# star.net
KiCad netlist of a schematic drawn in EAGLE
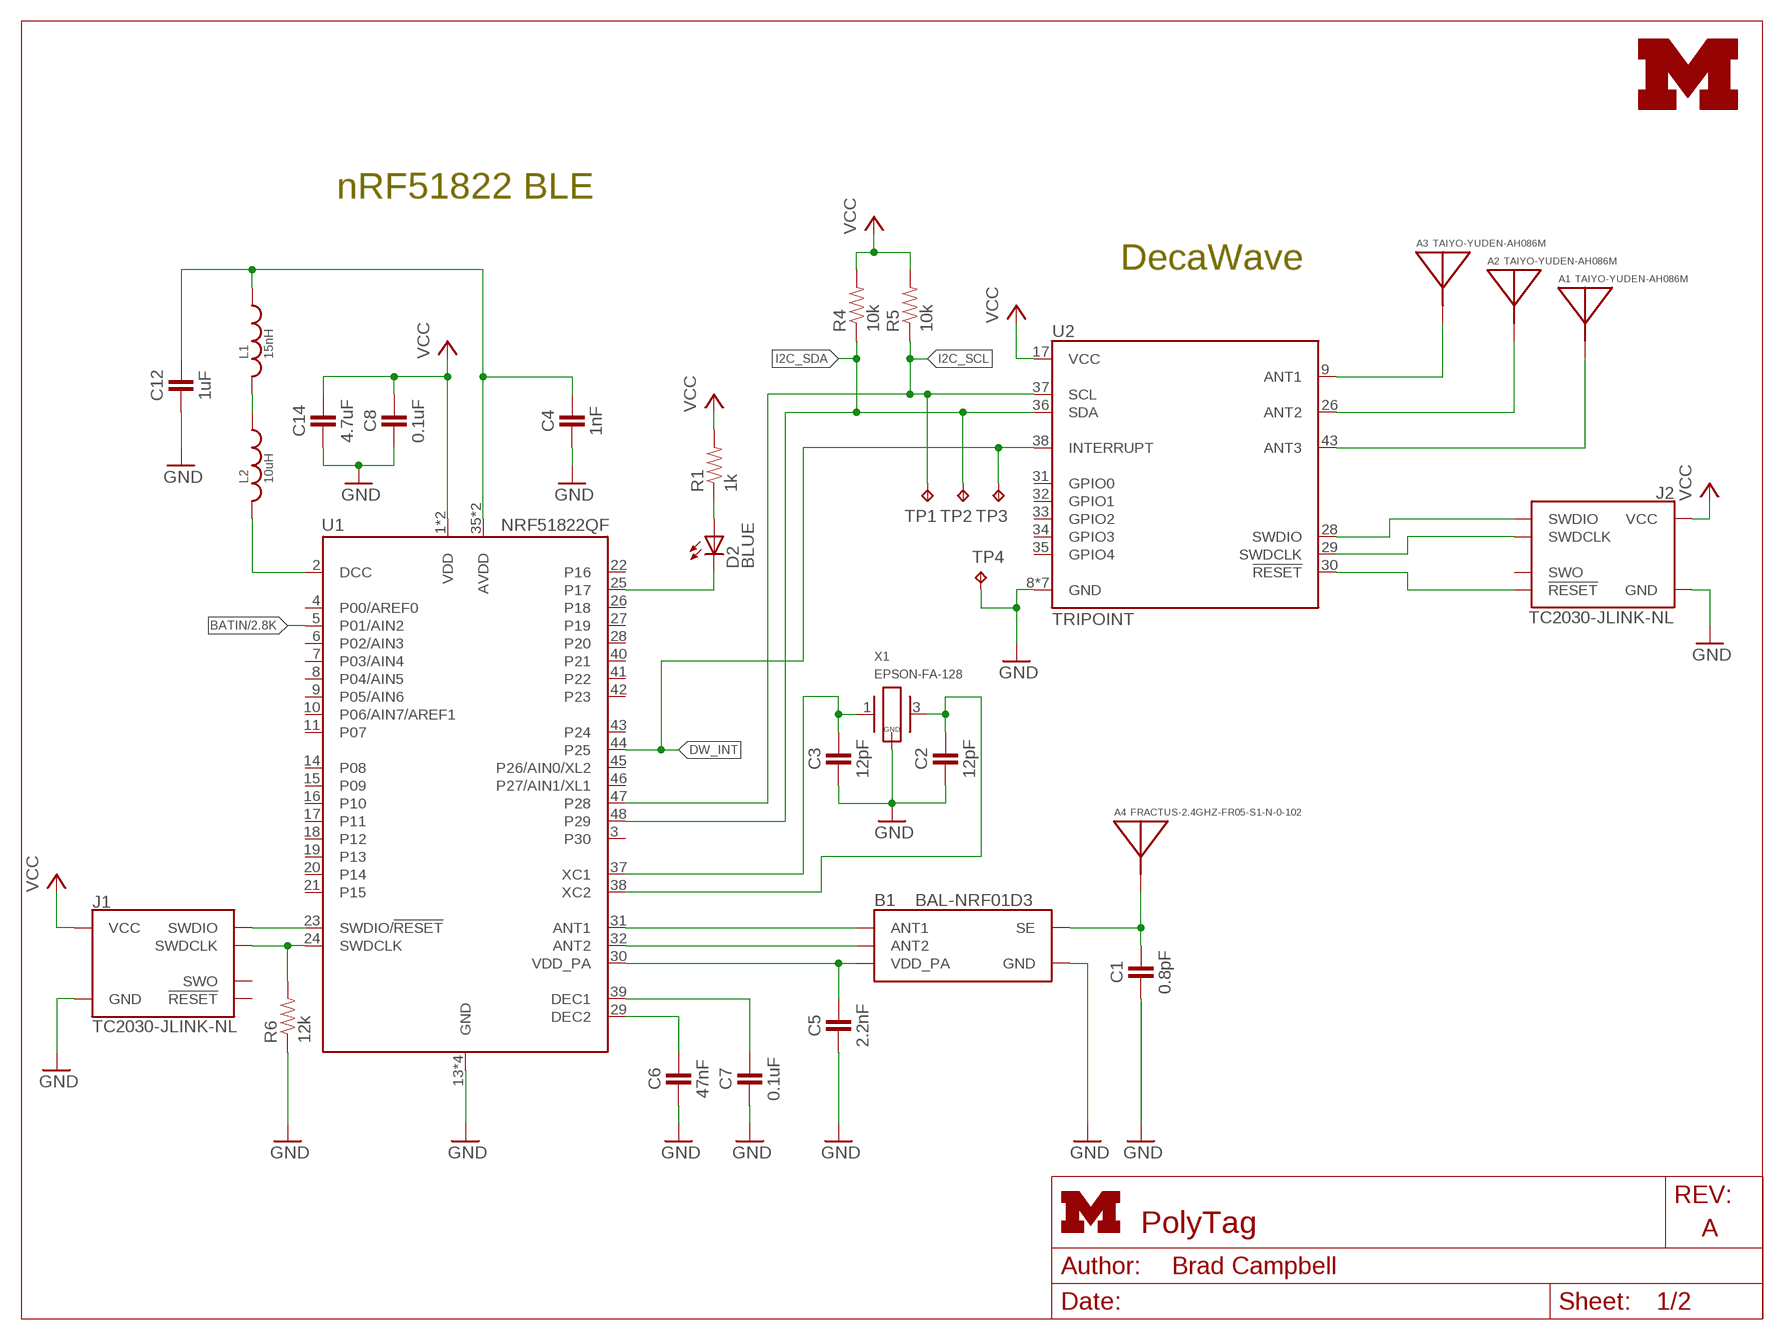
[diagram p0: schematic, sheet 1]
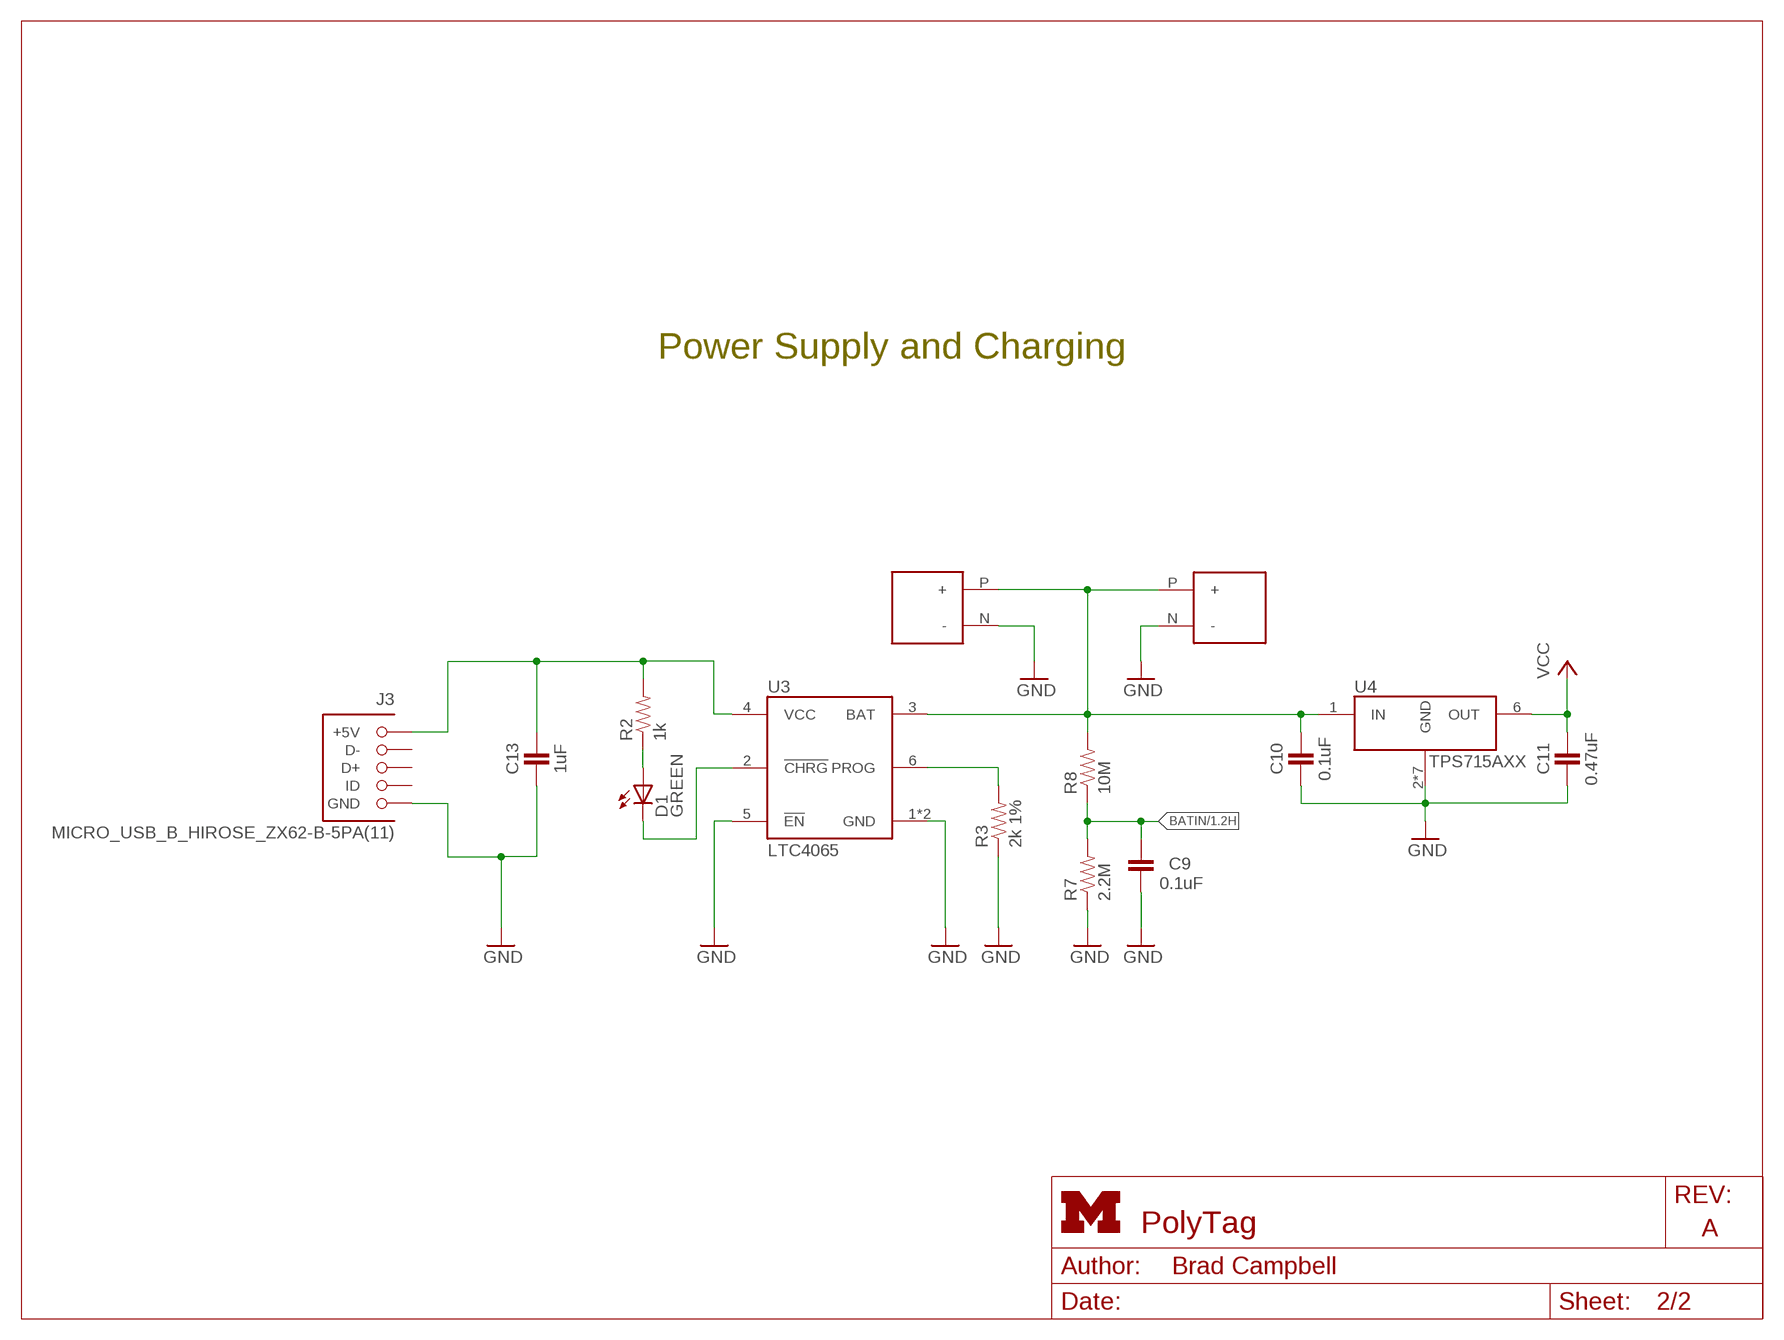
[diagram p1: schematic, sheet 2]

(export (version "E")
  (design (tool "Eeschema 10.0.6"))
  (components
    (comp (ref "A1")
      (value "TAIYO-YUDEN-AH086M")
      (footprint "eagle-import:TAIYO-YUDEN-AH086M")
      (libsource (lib "eagle-import") (part "TAIYO-YUDEN-AH086M"))
    )
    (comp (ref "A2")
      (value "TAIYO-YUDEN-AH086M")
      (footprint "eagle-import:TAIYO-YUDEN-AH086M")
      (libsource (lib "eagle-import") (part "TAIYO-YUDEN-AH086M"))
    )
    (comp (ref "A3")
      (value "TAIYO-YUDEN-AH086M")
      (footprint "eagle-import:TAIYO-YUDEN-AH086M")
      (libsource (lib "eagle-import") (part "TAIYO-YUDEN-AH086M"))
    )
    (comp (ref "A4")
      (value "FRACTUS-2.4GHZ-FR05-S1-N-0-102")
      (footprint "eagle-import:FRACTUS-ANTENNA-FR05-S1-N-0-102")
      (libsource (lib "eagle-import") (part "FRACTUS-2.4GHZ-FR05-S1-N-0-102"))
    )
    (comp (ref "B1")
      (value "BAL-NRF01D3")
      (footprint "eagle-import:BAL-NRF01D3")
      (libsource (lib "eagle-import") (part "BAL-NRF01D3"))
    )
    (comp (ref "C1")
      (value "0.8pF")
      (footprint "eagle-import:0402_CAP")
      (libsource (lib "eagle-import") (part "CAPACITOR"))
    )
    (comp (ref "C2")
      (value "12pF")
      (footprint "eagle-import:0402_CAP")
      (libsource (lib "eagle-import") (part "CAPACITOR"))
    )
    (comp (ref "C3")
      (value "12pF")
      (footprint "eagle-import:0402_CAP")
      (libsource (lib "eagle-import") (part "CAPACITOR"))
    )
    (comp (ref "C4")
      (value "1nF")
      (footprint "eagle-import:0402_CAP")
      (libsource (lib "eagle-import") (part "CAPACITOR"))
    )
    (comp (ref "C5")
      (value "2.2nF")
      (footprint "eagle-import:0402_CAP")
      (libsource (lib "eagle-import") (part "CAPACITOR"))
    )
    (comp (ref "C6")
      (value "47nF")
      (footprint "eagle-import:0402_CAP")
      (libsource (lib "eagle-import") (part "CAPACITOR"))
    )
    (comp (ref "C7")
      (value "0.1uF")
      (footprint "eagle-import:0402_CAP")
      (libsource (lib "eagle-import") (part "CAPACITOR"))
    )
    (comp (ref "C8")
      (value "0.1uF")
      (footprint "eagle-import:0402_CAP")
      (libsource (lib "eagle-import") (part "CAPACITOR"))
    )
    (comp (ref "C12")
      (value "1uF")
      (footprint "eagle-import:0402_CAP")
      (libsource (lib "eagle-import") (part "CAPACITOR"))
    )
    (comp (ref "C14")
      (value "4.7uF")
      (footprint "eagle-import:0402_CAP")
      (libsource (lib "eagle-import") (part "CAPACITOR"))
    )
    (comp (ref "D2")
      (value "BLUE")
      (footprint "eagle-import:LED-0603")
      (libsource (lib "eagle-import") (part "LED0603"))
    )
    (comp (ref "J1")
      (value "TC2030-JLINK-NL")
      (footprint "eagle-import:TC2030-IDC-NL")
      (libsource (lib "eagle-import") (part "TC2030-JLINK-NL"))
    )
    (comp (ref "J2")
      (value "TC2030-JLINK-NL")
      (footprint "eagle-import:TC2030-IDC-NL")
      (libsource (lib "eagle-import") (part "TC2030-JLINK-NL"))
    )
    (comp (ref "L1")
      (value "15nH")
      (footprint "eagle-import:0402_CAP")
      (libsource (lib "eagle-import") (part "INDUCTOR0402"))
    )
    (comp (ref "L2")
      (value "10uH")
      (footprint "eagle-import:0603_CAP")
      (libsource (lib "eagle-import") (part "INDUCTOR0603"))
    )
    (comp (ref "LOGO1")
      (value "UMICH_SOLID_SMALL")
      (footprint "eagle-import:UMICH_SOLID_75MIL")
      (libsource (lib "eagle-import") (part "UMICH_SOLID_SMALL"))
    )
    (comp (ref "R1")
      (value "1k")
      (footprint "eagle-import:0402_RES")
      (libsource (lib "eagle-import") (part "RESISTOR0402_RES"))
    )
    (comp (ref "R4")
      (value "10k")
      (footprint "eagle-import:0402_RES")
      (libsource (lib "eagle-import") (part "RESISTOR0402_RES"))
    )
    (comp (ref "R5")
      (value "10k")
      (footprint "eagle-import:0402_RES")
      (libsource (lib "eagle-import") (part "RESISTOR0402_RES"))
    )
    (comp (ref "R6")
      (value "12k")
      (footprint "eagle-import:0402_RES")
      (libsource (lib "eagle-import") (part "RESISTOR0402_RES"))
    )
    (comp (ref "TP1")
      (value "TPTP06SQ")
      (footprint "eagle-import:TP06SQ")
      (libsource (lib "eagle-import") (part "TPTP06SQ"))
    )
    (comp (ref "TP2")
      (value "TPTP06SQ")
      (footprint "eagle-import:TP06SQ")
      (libsource (lib "eagle-import") (part "TPTP06SQ"))
    )
    (comp (ref "TP3")
      (value "TPTP06SQ")
      (footprint "eagle-import:TP06SQ")
      (libsource (lib "eagle-import") (part "TPTP06SQ"))
    )
    (comp (ref "TP4")
      (value "TPTP06SQ")
      (footprint "eagle-import:TP06SQ")
      (libsource (lib "eagle-import") (part "TPTP06SQ"))
    )
    (comp (ref "U1")
      (value "NRF51822QF")
      (footprint "eagle-import:QFN-48-6MM")
      (libsource (lib "eagle-import") (part "NRF51822QF"))
    )
    (comp (ref "U2")
      (value "TRIPOINT")
      (footprint "eagle-import:TRIPOINT")
      (libsource (lib "eagle-import") (part "TRIPOINT"))
    )
    (comp (ref "X1")
      (value "EPSON-FA-128")
      (footprint "eagle-import:FA-128")
      (libsource (lib "eagle-import") (part "EPSON-FA-128"))
    )
    (comp (ref "C9")
      (value "0.1uF")
      (footprint "eagle-import:0402_CAP")
      (libsource (lib "eagle-import") (part "CAPACITOR"))
    )
    (comp (ref "C10")
      (value "0.1uF")
      (footprint "eagle-import:0402_CAP")
      (libsource (lib "eagle-import") (part "CAPACITOR"))
    )
    (comp (ref "C11")
      (value "0.47uF")
      (footprint "eagle-import:0402_CAP")
      (libsource (lib "eagle-import") (part "CAPACITOR"))
    )
    (comp (ref "C13")
      (value "1uF")
      (footprint "eagle-import:0402_CAP")
      (libsource (lib "eagle-import") (part "CAPACITOR"))
    )
    (comp (ref "D1")
      (value "GREEN")
      (footprint "eagle-import:LED-0603")
      (libsource (lib "eagle-import") (part "LED0603"))
    )
    (comp (ref "J3")
      (value "MICRO_USB_B_HIROSE_ZX62-B-5PA(11)")
      (footprint "eagle-import:USB_MICRO_B-HIROSE-ZX62-B-5PA(11)")
      (libsource (lib "eagle-import") (part "MICRO_USB_B_HIROSE_ZX62-B-5PA(11)"))
    )
    (comp (ref "J4")
      (value "BAT_HOLE")
      (footprint "eagle-import:BATTERY_HOLE")
      (libsource (lib "eagle-import") (part "BAT_HOLE"))
    )
    (comp (ref "J5")
      (value "BAT_HOLE")
      (footprint "eagle-import:BATTERY_HOLE")
      (libsource (lib "eagle-import") (part "BAT_HOLE"))
    )
    (comp (ref "R2")
      (value "1k")
      (footprint "eagle-import:0402_RES")
      (libsource (lib "eagle-import") (part "RESISTOR0402_RES"))
    )
    (comp (ref "R3")
      (value "2k 1%")
      (footprint "eagle-import:0402_RES")
      (libsource (lib "eagle-import") (part "RESISTOR0402_RES"))
    )
    (comp (ref "R7")
      (value "2.2M")
      (footprint "eagle-import:0402_RES")
      (libsource (lib "eagle-import") (part "RESISTOR0402_RES"))
    )
    (comp (ref "R8")
      (value "10M")
      (footprint "eagle-import:0402_RES")
      (libsource (lib "eagle-import") (part "RESISTOR0402_RES"))
    )
    (comp (ref "U3")
      (value "LTC4065")
      (footprint "eagle-import:DFN-6_2MM")
      (libsource (lib "eagle-import") (part "LTC4065"))
    )
    (comp (ref "U4")
      (value "TPS715AXX")
      (footprint "eagle-import:WDFN-6")
      (libsource (lib "eagle-import") (part "TPS715AXX"))
    )
  )
  (nets
    (net (code "1") (name "BATIN") (class "Default")
      (node (ref "C9") (pin "2") (pinfunction "2_2") (pintype "bidirectional"))
      (node (ref "R7") (pin "2") (pinfunction "2_2") (pintype "passive"))
      (node (ref "R8") (pin "1") (pinfunction "1_1") (pintype "passive"))
      (node (ref "U1") (pin "5") (pinfunction "P01/AIN2_5") (pintype "bidirectional"))
    )
    (net (code "2") (name "DW_INT") (class "Default")
      (node (ref "TP3") (pin "TP") (pinfunction "TP_TP") (pintype "input"))
      (node (ref "U1") (pin "44") (pinfunction "P25_44") (pintype "bidirectional"))
      (node (ref "U2") (pin "38") (pinfunction "INTERRUPT_38") (pintype "bidirectional"))
    )
    (net (code "3") (name "GND") (class "Default")
      (node (ref "B1") (pin "GND") (pinfunction "GND_GND") (pintype "bidirectional"))
      (node (ref "C1") (pin "2") (pinfunction "2_2") (pintype "bidirectional"))
      (node (ref "C10") (pin "2") (pinfunction "2_2") (pintype "bidirectional"))
      (node (ref "C11") (pin "2") (pinfunction "2_2") (pintype "bidirectional"))
      (node (ref "C12") (pin "2") (pinfunction "2_2") (pintype "bidirectional"))
      (node (ref "C13") (pin "2") (pinfunction "2_2") (pintype "bidirectional"))
      (node (ref "C14") (pin "2") (pinfunction "2_2") (pintype "bidirectional"))
      (node (ref "C2") (pin "2") (pinfunction "2_2") (pintype "bidirectional"))
      (node (ref "C3") (pin "2") (pinfunction "2_2") (pintype "bidirectional"))
      (node (ref "C4") (pin "2") (pinfunction "2_2") (pintype "bidirectional"))
      (node (ref "C5") (pin "2") (pinfunction "2_2") (pintype "bidirectional"))
      (node (ref "C6") (pin "2") (pinfunction "2_2") (pintype "bidirectional"))
      (node (ref "C7") (pin "2") (pinfunction "2_2") (pintype "bidirectional"))
      (node (ref "C8") (pin "2") (pinfunction "2_2") (pintype "bidirectional"))
      (node (ref "C9") (pin "1") (pinfunction "1_1") (pintype "bidirectional"))
      (node (ref "J1") (pin "5") (pinfunction "GND_5") (pintype "bidirectional"))
      (node (ref "J2") (pin "5") (pinfunction "GND_5") (pintype "bidirectional"))
      (node (ref "J3") (pin "5") (pinfunction "GND_5") (pintype "bidirectional"))
      (node (ref "J4") (pin "N") (pinfunction "-_N") (pintype "bidirectional"))
      (node (ref "J5") (pin "N") (pinfunction "-_N") (pintype "bidirectional"))
      (node (ref "R3") (pin "1") (pinfunction "1_1") (pintype "passive"))
      (node (ref "R6") (pin "1") (pinfunction "1_1") (pintype "passive"))
      (node (ref "R7") (pin "1") (pinfunction "1_1") (pintype "passive"))
      (node (ref "TP4") (pin "TP") (pinfunction "TP_TP") (pintype "input"))
      (node (ref "U1") (pin "13") (pinfunction "GND_13") (pintype "bidirectional"))
      (node (ref "U1") (pin "33") (pinfunction "GND_33") (pintype "bidirectional"))
      (node (ref "U1") (pin "34") (pinfunction "GND_34") (pintype "bidirectional"))
      (node (ref "U1") (pin "GND") (pinfunction "GND_GND") (pintype "bidirectional"))
      (node (ref "U2") (pin "10") (pinfunction "GND_10") (pintype "bidirectional"))
      (node (ref "U2") (pin "18") (pinfunction "GND_18") (pintype "bidirectional"))
      (node (ref "U2") (pin "25") (pinfunction "GND_25") (pintype "bidirectional"))
      (node (ref "U2") (pin "27") (pinfunction "GND_27") (pintype "bidirectional"))
      (node (ref "U2") (pin "42") (pinfunction "GND_42") (pintype "bidirectional"))
      (node (ref "U2") (pin "44") (pinfunction "GND_44") (pintype "bidirectional"))
      (node (ref "U2") (pin "8") (pinfunction "GND_8") (pintype "bidirectional"))
      (node (ref "U3") (pin "1") (pinfunction "GND_1") (pintype "bidirectional"))
      (node (ref "U3") (pin "5") (pinfunction "~{EN}_5") (pintype "bidirectional"))
      (node (ref "U3") (pin "7") (pinfunction "GND_7") (pintype "bidirectional"))
      (node (ref "U4") (pin "2") (pinfunction "GND_2") (pintype "bidirectional"))
      (node (ref "U4") (pin "3") (pinfunction "GND_3") (pintype "bidirectional"))
      (node (ref "U4") (pin "4") (pinfunction "GND_4") (pintype "bidirectional"))
      (node (ref "U4") (pin "5") (pinfunction "GND_5") (pintype "bidirectional"))
      (node (ref "U4") (pin "TP") (pinfunction "GND_TP") (pintype "bidirectional"))
      (node (ref "U4") (pin "TP2") (pinfunction "GND_TP2") (pintype "bidirectional"))
      (node (ref "U4") (pin "TP3") (pinfunction "GND_TP3") (pintype "bidirectional"))
      (node (ref "X1") (pin "2") (pinfunction "GND_2") (pintype "bidirectional"))
      (node (ref "X1") (pin "4") (pinfunction "GND_4") (pintype "bidirectional"))
    )
    (net (code "4") (name "I2C_SCL") (class "Default")
      (node (ref "R5") (pin "1") (pinfunction "1_1") (pintype "passive"))
      (node (ref "TP1") (pin "TP") (pinfunction "TP_TP") (pintype "input"))
      (node (ref "U1") (pin "47") (pinfunction "P28_47") (pintype "bidirectional"))
      (node (ref "U2") (pin "37") (pinfunction "SCL_37") (pintype "bidirectional"))
    )
    (net (code "5") (name "I2C_SDA") (class "Default")
      (node (ref "R4") (pin "1") (pinfunction "1_1") (pintype "passive"))
      (node (ref "TP2") (pin "TP") (pinfunction "TP_TP") (pintype "input"))
      (node (ref "U1") (pin "48") (pinfunction "P29_48") (pintype "bidirectional"))
      (node (ref "U2") (pin "36") (pinfunction "SDA_36") (pintype "bidirectional"))
    )
    (net (code "6") (name "Net-(A1-ANTENNA)") (class "Default")
      (node (ref "A1") (pin "A") (pinfunction "ANTENNA_A") (pintype "bidirectional"))
      (node (ref "U2") (pin "43") (pinfunction "ANT3_43") (pintype "bidirectional"))
    )
    (net (code "7") (name "Net-(A2-ANTENNA)") (class "Default")
      (node (ref "A2") (pin "A") (pinfunction "ANTENNA_A") (pintype "bidirectional"))
      (node (ref "U2") (pin "26") (pinfunction "ANT2_26") (pintype "bidirectional"))
    )
    (net (code "8") (name "Net-(A3-ANTENNA)") (class "Default")
      (node (ref "A3") (pin "A") (pinfunction "ANTENNA_A") (pintype "bidirectional"))
      (node (ref "U2") (pin "9") (pinfunction "ANT1_9") (pintype "bidirectional"))
    )
    (net (code "9") (name "Net-(A4-ANTENNA)") (class "Default")
      (node (ref "A4") (pin "1") (pinfunction "ANTENNA_1") (pintype "bidirectional"))
      (node (ref "B1") (pin "SE") (pinfunction "SE_SE") (pintype "bidirectional"))
      (node (ref "C1") (pin "1") (pinfunction "1_1") (pintype "bidirectional"))
    )
    (net (code "10") (name "Net-(B1-VDD_PA)") (class "Default")
      (node (ref "B1") (pin "VCC") (pinfunction "VDD_PA_VCC") (pintype "bidirectional"))
      (node (ref "C5") (pin "1") (pinfunction "1_1") (pintype "bidirectional"))
      (node (ref "U1") (pin "30") (pinfunction "VDD_PA_30") (pintype "bidirectional"))
    )
    (net (code "11") (name "Net-(C12-Pad1)") (class "Default")
      (node (ref "C12") (pin "1") (pinfunction "1_1") (pintype "bidirectional"))
      (node (ref "C4") (pin "1") (pinfunction "1_1") (pintype "bidirectional"))
      (node (ref "L1") (pin "1") (pinfunction "1_1") (pintype "bidirectional"))
      (node (ref "U1") (pin "35") (pinfunction "AVDD_35") (pintype "bidirectional"))
      (node (ref "U1") (pin "36") (pinfunction "AVDD_36") (pintype "bidirectional"))
    )
    (net (code "12") (name "Net-(D1-PadA)") (class "Default")
      (node (ref "D1") (pin "A") (pinfunction "A_A") (pintype "passive"))
      (node (ref "R2") (pin "1") (pinfunction "1_1") (pintype "passive"))
    )
    (net (code "13") (name "Net-(D2-PadA)") (class "Default")
      (node (ref "D2") (pin "A") (pinfunction "A_A") (pintype "passive"))
      (node (ref "R1") (pin "1") (pinfunction "1_1") (pintype "passive"))
    )
    (net (code "14") (name "Net-(J1-SWDCLK)") (class "Default")
      (node (ref "J1") (pin "4") (pinfunction "SWDCLK_4") (pintype "bidirectional"))
      (node (ref "R6") (pin "2") (pinfunction "2_2") (pintype "passive"))
      (node (ref "U1") (pin "24") (pinfunction "SWDCLK_24") (pintype "bidirectional"))
    )
    (net (code "15") (name "Net-(J1-SWDIO)") (class "Default")
      (node (ref "J1") (pin "2") (pinfunction "SWDIO_2") (pintype "bidirectional"))
      (node (ref "U1") (pin "23") (pinfunction "SWDIO/~{RESET}_23") (pintype "bidirectional"))
    )
    (net (code "16") (name "Net-(J2-SWDCLK)") (class "Default")
      (node (ref "J2") (pin "4") (pinfunction "SWDCLK_4") (pintype "bidirectional"))
      (node (ref "U2") (pin "29") (pinfunction "SWDCLK_29") (pintype "bidirectional"))
    )
    (net (code "17") (name "Net-(J2-SWDIO)") (class "Default")
      (node (ref "J2") (pin "2") (pinfunction "SWDIO_2") (pintype "bidirectional"))
      (node (ref "U2") (pin "28") (pinfunction "SWDIO_28") (pintype "bidirectional"))
    )
    (net (code "18") (name "Net-(J2-~{RESET})") (class "Default")
      (node (ref "J2") (pin "3") (pinfunction "~{RESET}_3") (pintype "bidirectional"))
      (node (ref "U2") (pin "30") (pinfunction "~{RESET}_30") (pintype "bidirectional"))
    )
    (net (code "19") (name "Net-(J3-+5V)") (class "Default")
      (node (ref "C13") (pin "1") (pinfunction "1_1") (pintype "bidirectional"))
      (node (ref "J3") (pin "1") (pinfunction "+5V_1") (pintype "bidirectional"))
      (node (ref "R2") (pin "2") (pinfunction "2_2") (pintype "passive"))
      (node (ref "U3") (pin "4") (pinfunction "VCC_4") (pintype "bidirectional"))
    )
    (net (code "20") (name "Net-(J4-+)") (class "Default")
      (node (ref "C10") (pin "1") (pinfunction "1_1") (pintype "bidirectional"))
      (node (ref "J4") (pin "P") (pinfunction "+_P") (pintype "bidirectional"))
      (node (ref "J5") (pin "P") (pinfunction "+_P") (pintype "bidirectional"))
      (node (ref "R8") (pin "2") (pinfunction "2_2") (pintype "passive"))
      (node (ref "U3") (pin "3") (pinfunction "BAT_3") (pintype "bidirectional"))
      (node (ref "U4") (pin "1") (pinfunction "IN_1") (pintype "bidirectional"))
    )
    (net (code "21") (name "Net-(L1-Pad2)") (class "Default")
      (node (ref "L1") (pin "2") (pinfunction "2_2") (pintype "bidirectional"))
      (node (ref "L2") (pin "1") (pinfunction "1_1") (pintype "bidirectional"))
    )
    (net (code "22") (name "Net-(U1-ANT1)") (class "Default")
      (node (ref "B1") (pin "ANT1") (pinfunction "ANT1_ANT1") (pintype "bidirectional"))
      (node (ref "U1") (pin "31") (pinfunction "ANT1_31") (pintype "bidirectional"))
    )
    (net (code "23") (name "Net-(U1-ANT2)") (class "Default")
      (node (ref "B1") (pin "ANT2") (pinfunction "ANT2_ANT2") (pintype "bidirectional"))
      (node (ref "U1") (pin "32") (pinfunction "ANT2_32") (pintype "bidirectional"))
    )
    (net (code "24") (name "Net-(U1-DCC)") (class "Default")
      (node (ref "L2") (pin "2") (pinfunction "2_2") (pintype "bidirectional"))
      (node (ref "U1") (pin "2") (pinfunction "DCC_2") (pintype "bidirectional"))
    )
    (net (code "25") (name "Net-(U1-DEC1)") (class "Default")
      (node (ref "C7") (pin "1") (pinfunction "1_1") (pintype "bidirectional"))
      (node (ref "U1") (pin "39") (pinfunction "DEC1_39") (pintype "bidirectional"))
    )
    (net (code "26") (name "Net-(U1-DEC2)") (class "Default")
      (node (ref "C6") (pin "1") (pinfunction "1_1") (pintype "bidirectional"))
      (node (ref "U1") (pin "29") (pinfunction "DEC2_29") (pintype "bidirectional"))
    )
    (net (code "27") (name "Net-(U1-P17)") (class "Default")
      (node (ref "D2") (pin "C") (pinfunction "C_C") (pintype "passive"))
      (node (ref "U1") (pin "25") (pinfunction "P17_25") (pintype "bidirectional"))
    )
    (net (code "28") (name "Net-(U1-XC1)") (class "Default")
      (node (ref "C3") (pin "1") (pinfunction "1_1") (pintype "bidirectional"))
      (node (ref "U1") (pin "37") (pinfunction "XC1_37") (pintype "bidirectional"))
      (node (ref "X1") (pin "1") (pinfunction "1_1") (pintype "bidirectional"))
    )
    (net (code "29") (name "Net-(U1-XC2)") (class "Default")
      (node (ref "C2") (pin "1") (pinfunction "1_1") (pintype "bidirectional"))
      (node (ref "U1") (pin "38") (pinfunction "XC2_38") (pintype "bidirectional"))
      (node (ref "X1") (pin "3") (pinfunction "2_3") (pintype "bidirectional"))
    )
    (net (code "30") (name "Net-(U3-PROG)") (class "Default")
      (node (ref "R3") (pin "2") (pinfunction "2_2") (pintype "passive"))
      (node (ref "U3") (pin "6") (pinfunction "PROG_6") (pintype "bidirectional"))
    )
    (net (code "31") (name "Net-(U3-~{CHRG})") (class "Default")
      (node (ref "D1") (pin "C") (pinfunction "C_C") (pintype "passive"))
      (node (ref "U3") (pin "2") (pinfunction "~{CHRG}_2") (pintype "bidirectional"))
    )
    (net (code "32") (name "VCC") (class "Default")
      (node (ref "C11") (pin "1") (pinfunction "1_1") (pintype "bidirectional"))
      (node (ref "C14") (pin "1") (pinfunction "1_1") (pintype "bidirectional"))
      (node (ref "C8") (pin "1") (pinfunction "1_1") (pintype "bidirectional"))
      (node (ref "J1") (pin "1") (pinfunction "VCC_1") (pintype "bidirectional"))
      (node (ref "J2") (pin "1") (pinfunction "VCC_1") (pintype "bidirectional"))
      (node (ref "R1") (pin "2") (pinfunction "2_2") (pintype "passive"))
      (node (ref "R4") (pin "2") (pinfunction "2_2") (pintype "passive"))
      (node (ref "R5") (pin "2") (pinfunction "2_2") (pintype "passive"))
      (node (ref "U1") (pin "1") (pinfunction "VDD_1") (pintype "bidirectional"))
      (node (ref "U1") (pin "12") (pinfunction "VDD_12") (pintype "bidirectional"))
      (node (ref "U2") (pin "17") (pinfunction "VCC_17") (pintype "bidirectional"))
      (node (ref "U4") (pin "6") (pinfunction "OUT_6") (pintype "bidirectional"))
    )
    (net (code "33") (name "unconnected-(J1-SWO-Pad6)") (class "Default")
      (node (ref "J1") (pin "6") (pinfunction "SWO_6") (pintype "bidirectional"))
    )
    (net (code "34") (name "unconnected-(J1-~{RESET}-Pad3)") (class "Default")
      (node (ref "J1") (pin "3") (pinfunction "~{RESET}_3") (pintype "bidirectional"))
    )
    (net (code "35") (name "unconnected-(J2-SWO-Pad6)") (class "Default")
      (node (ref "J2") (pin "6") (pinfunction "SWO_6") (pintype "bidirectional"))
    )
    (net (code "36") (name "unconnected-(J3-D+-Pad3)") (class "Default")
      (node (ref "J3") (pin "3") (pinfunction "D+_3") (pintype "bidirectional"))
    )
    (net (code "37") (name "unconnected-(J3-D--Pad2)") (class "Default")
      (node (ref "J3") (pin "2") (pinfunction "D-_2") (pintype "bidirectional"))
    )
    (net (code "38") (name "unconnected-(J3-ID-Pad4)") (class "Default")
      (node (ref "J3") (pin "4") (pinfunction "ID_4") (pintype "bidirectional"))
    )
    (net (code "39") (name "unconnected-(U1-P00{slash}AREF0-Pad4)") (class "Default")
      (node (ref "U1") (pin "4") (pinfunction "P00/AREF0_4") (pintype "bidirectional"))
    )
    (net (code "40") (name "unconnected-(U1-P02{slash}AIN3-Pad6)") (class "Default")
      (node (ref "U1") (pin "6") (pinfunction "P02/AIN3_6") (pintype "bidirectional"))
    )
    (net (code "41") (name "unconnected-(U1-P03{slash}AIN4-Pad7)") (class "Default")
      (node (ref "U1") (pin "7") (pinfunction "P03/AIN4_7") (pintype "bidirectional"))
    )
    (net (code "42") (name "unconnected-(U1-P04{slash}AIN5-Pad8)") (class "Default")
      (node (ref "U1") (pin "8") (pinfunction "P04/AIN5_8") (pintype "bidirectional"))
    )
    (net (code "43") (name "unconnected-(U1-P05{slash}AIN6-Pad9)") (class "Default")
      (node (ref "U1") (pin "9") (pinfunction "P05/AIN6_9") (pintype "bidirectional"))
    )
    (net (code "44") (name "unconnected-(U1-P06{slash}AIN7{slash}AREF1-Pad10)") (class "Default")
      (node (ref "U1") (pin "10") (pinfunction "P06/AIN7/AREF1_10") (pintype "bidirectional"))
    )
    (net (code "45") (name "unconnected-(U1-P07-Pad11)") (class "Default")
      (node (ref "U1") (pin "11") (pinfunction "P07_11") (pintype "bidirectional"))
    )
    (net (code "46") (name "unconnected-(U1-P08-Pad14)") (class "Default")
      (node (ref "U1") (pin "14") (pinfunction "P08_14") (pintype "bidirectional"))
    )
    (net (code "47") (name "unconnected-(U1-P09-Pad15)") (class "Default")
      (node (ref "U1") (pin "15") (pinfunction "P09_15") (pintype "bidirectional"))
    )
    (net (code "48") (name "unconnected-(U1-P10-Pad16)") (class "Default")
      (node (ref "U1") (pin "16") (pinfunction "P10_16") (pintype "bidirectional"))
    )
    (net (code "49") (name "unconnected-(U1-P11-Pad17)") (class "Default")
      (node (ref "U1") (pin "17") (pinfunction "P11_17") (pintype "bidirectional"))
    )
    (net (code "50") (name "unconnected-(U1-P12-Pad18)") (class "Default")
      (node (ref "U1") (pin "18") (pinfunction "P12_18") (pintype "bidirectional"))
    )
    (net (code "51") (name "unconnected-(U1-P13-Pad19)") (class "Default")
      (node (ref "U1") (pin "19") (pinfunction "P13_19") (pintype "bidirectional"))
    )
    (net (code "52") (name "unconnected-(U1-P14-Pad20)") (class "Default")
      (node (ref "U1") (pin "20") (pinfunction "P14_20") (pintype "bidirectional"))
    )
    (net (code "53") (name "unconnected-(U1-P15-Pad21)") (class "Default")
      (node (ref "U1") (pin "21") (pinfunction "P15_21") (pintype "bidirectional"))
    )
    (net (code "54") (name "unconnected-(U1-P16-Pad22)") (class "Default")
      (node (ref "U1") (pin "22") (pinfunction "P16_22") (pintype "bidirectional"))
    )
    (net (code "55") (name "unconnected-(U1-P18-Pad26)") (class "Default")
      (node (ref "U1") (pin "26") (pinfunction "P18_26") (pintype "bidirectional"))
    )
    (net (code "56") (name "unconnected-(U1-P19-Pad27)") (class "Default")
      (node (ref "U1") (pin "27") (pinfunction "P19_27") (pintype "bidirectional"))
    )
    (net (code "57") (name "unconnected-(U1-P20-Pad28)") (class "Default")
      (node (ref "U1") (pin "28") (pinfunction "P20_28") (pintype "bidirectional"))
    )
    (net (code "58") (name "unconnected-(U1-P21-Pad40)") (class "Default")
      (node (ref "U1") (pin "40") (pinfunction "P21_40") (pintype "bidirectional"))
    )
    (net (code "59") (name "unconnected-(U1-P22-Pad41)") (class "Default")
      (node (ref "U1") (pin "41") (pinfunction "P22_41") (pintype "bidirectional"))
    )
    (net (code "60") (name "unconnected-(U1-P23-Pad42)") (class "Default")
      (node (ref "U1") (pin "42") (pinfunction "P23_42") (pintype "bidirectional"))
    )
    (net (code "61") (name "unconnected-(U1-P24-Pad43)") (class "Default")
      (node (ref "U1") (pin "43") (pinfunction "P24_43") (pintype "bidirectional"))
    )
    (net (code "62") (name "unconnected-(U1-P26{slash}AIN0{slash}XL2-Pad45)") (class "Default")
      (node (ref "U1") (pin "45") (pinfunction "P26/AIN0/XL2_45") (pintype "bidirectional"))
    )
    (net (code "63") (name "unconnected-(U1-P27{slash}AIN1{slash}XL1-Pad46)") (class "Default")
      (node (ref "U1") (pin "46") (pinfunction "P27/AIN1/XL1_46") (pintype "bidirectional"))
    )
    (net (code "64") (name "unconnected-(U1-P30-Pad3)") (class "Default")
      (node (ref "U1") (pin "3") (pinfunction "P30_3") (pintype "bidirectional"))
    )
    (net (code "65") (name "unconnected-(U2-GPIO0-Pad31)") (class "Default")
      (node (ref "U2") (pin "31") (pinfunction "GPIO0_31") (pintype "bidirectional"))
    )
    (net (code "66") (name "unconnected-(U2-GPIO1-Pad32)") (class "Default")
      (node (ref "U2") (pin "32") (pinfunction "GPIO1_32") (pintype "bidirectional"))
    )
    (net (code "67") (name "unconnected-(U2-GPIO2-Pad33)") (class "Default")
      (node (ref "U2") (pin "33") (pinfunction "GPIO2_33") (pintype "bidirectional"))
    )
    (net (code "68") (name "unconnected-(U2-GPIO3-Pad34)") (class "Default")
      (node (ref "U2") (pin "34") (pinfunction "GPIO3_34") (pintype "bidirectional"))
    )
    (net (code "69") (name "unconnected-(U2-GPIO4-Pad35)") (class "Default")
      (node (ref "U2") (pin "35") (pinfunction "GPIO4_35") (pintype "bidirectional"))
    )
  )
)
